# BLOCK1.net
KiCad netlist of a schematic drawn in Altium Designer
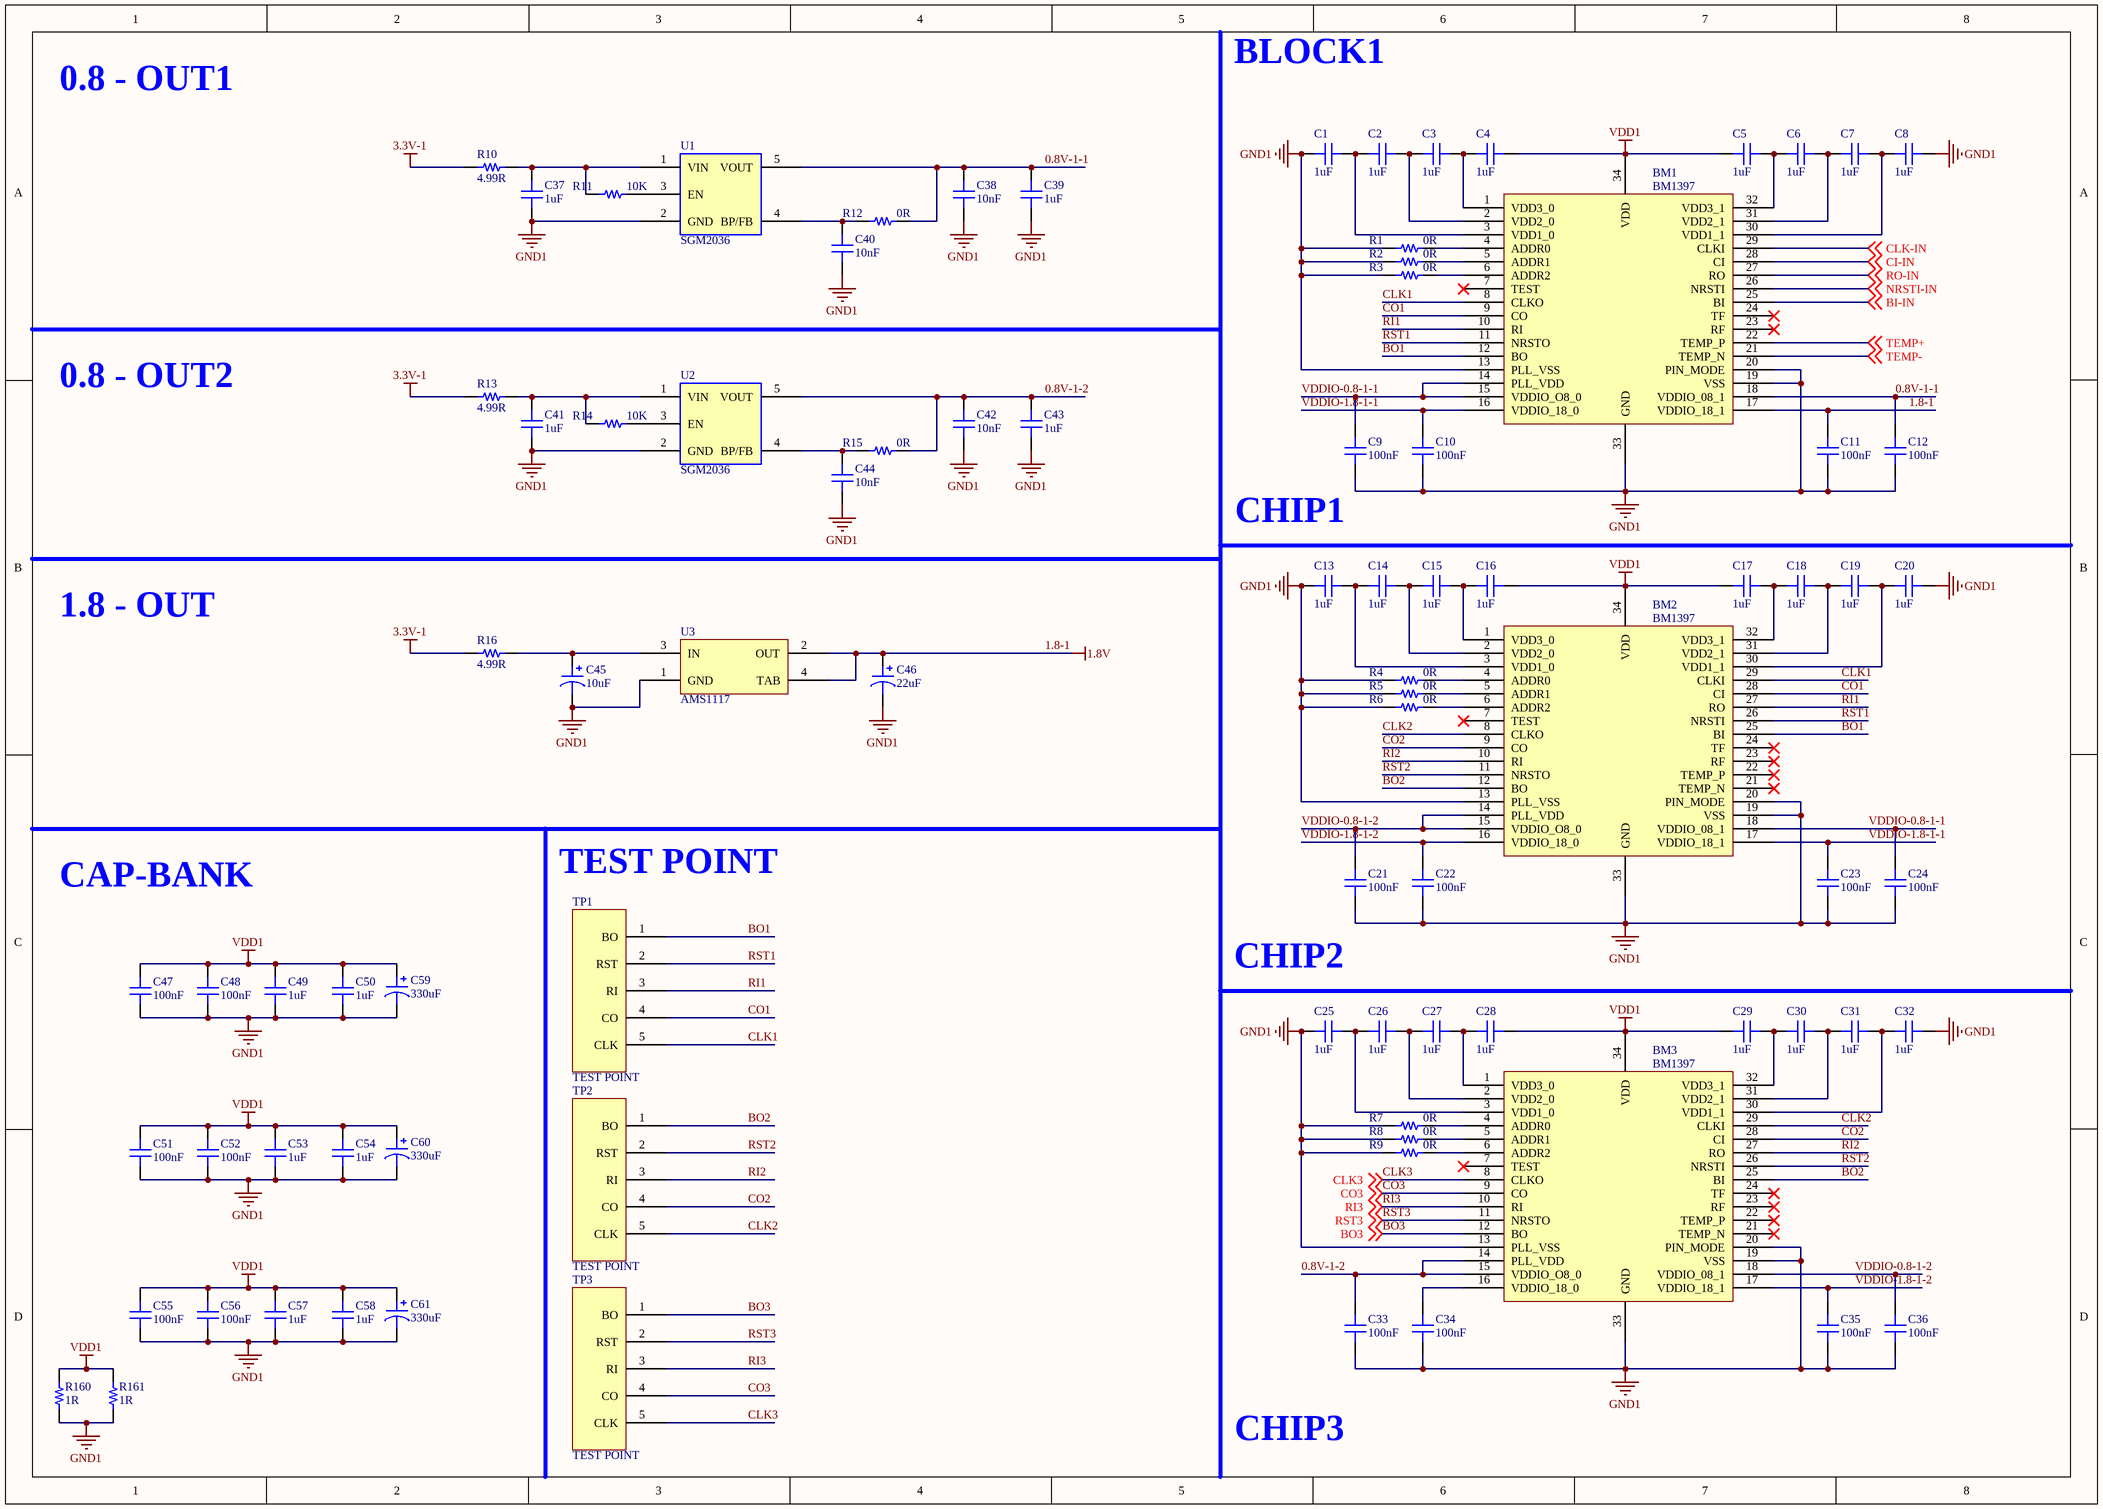
[diagram p0: BLOCK1.SchDoc]

(export (version "E")
  (design (tool "Eeschema 10.0.6"))
  (components
    (comp (ref "BM1") (value "BM1397") (footprint "BM1387") (libsource (lib "Miner_8TH") (part "BM1397_0")))
    (comp (ref "BM2") (value "BM1397") (footprint "BM1387") (libsource (lib "Miner_8TH") (part "BM1397_0")))
    (comp (ref "BM3") (value "BM1397") (footprint "BM1387") (libsource (lib "Miner_8TH") (part "BM1397_0")))
    (comp (ref "C1") (value "1uF") (footprint "CAP-SMD-0603") (libsource (lib "Miner_8TH") (part "CAP")))
    (comp (ref "C2") (value "1uF") (footprint "CAP-SMD-0603") (libsource (lib "Miner_8TH") (part "CAP")))
    (comp (ref "C3") (value "1uF") (footprint "CAP-SMD-0603") (libsource (lib "Miner_8TH") (part "CAP")))
    (comp (ref "C4") (value "1uF") (footprint "CAP-SMD-0603") (libsource (lib "Miner_8TH") (part "CAP")))
    (comp (ref "C5") (value "1uF") (footprint "CAP-SMD-0603") (libsource (lib "Miner_8TH") (part "CAP")))
    (comp (ref "C6") (value "1uF") (footprint "CAP-SMD-0603") (libsource (lib "Miner_8TH") (part "CAP")))
    (comp (ref "C7") (value "1uF") (footprint "CAP-SMD-0603") (libsource (lib "Miner_8TH") (part "CAP")))
    (comp (ref "C8") (value "1uF") (footprint "CAP-SMD-0603") (libsource (lib "Miner_8TH") (part "CAP")))
    (comp (ref "C9") (value "100nF") (footprint "CAP_SMD_0805") (libsource (lib "Miner_8TH") (part "CAP")))
    (comp (ref "C10") (value "100nF") (footprint "CAP_SMD_0805") (libsource (lib "Miner_8TH") (part "CAP")))
    (comp (ref "C11") (value "100nF") (footprint "CAP_SMD_0805") (libsource (lib "Miner_8TH") (part "CAP")))
    (comp (ref "C12") (value "100nF") (footprint "CAP_SMD_0805") (libsource (lib "Miner_8TH") (part "CAP")))
    (comp (ref "C13") (value "1uF") (footprint "CAP-SMD-0603") (libsource (lib "Miner_8TH") (part "CAP")))
    (comp (ref "C14") (value "1uF") (footprint "CAP-SMD-0603") (libsource (lib "Miner_8TH") (part "CAP")))
    (comp (ref "C15") (value "1uF") (footprint "CAP-SMD-0603") (libsource (lib "Miner_8TH") (part "CAP")))
    (comp (ref "C16") (value "1uF") (footprint "CAP-SMD-0603") (libsource (lib "Miner_8TH") (part "CAP")))
    (comp (ref "C17") (value "1uF") (footprint "CAP-SMD-0603") (libsource (lib "Miner_8TH") (part "CAP")))
    (comp (ref "C18") (value "1uF") (footprint "CAP-SMD-0603") (libsource (lib "Miner_8TH") (part "CAP")))
    (comp (ref "C19") (value "1uF") (footprint "CAP-SMD-0603") (libsource (lib "Miner_8TH") (part "CAP")))
    (comp (ref "C20") (value "1uF") (footprint "CAP-SMD-0603") (libsource (lib "Miner_8TH") (part "CAP")))
    (comp (ref "C21") (value "100nF") (footprint "CAP_SMD_0805") (libsource (lib "Miner_8TH") (part "CAP")))
    (comp (ref "C22") (value "100nF") (footprint "CAP_SMD_0805") (libsource (lib "Miner_8TH") (part "CAP")))
    (comp (ref "C23") (value "100nF") (footprint "CAP_SMD_0805") (libsource (lib "Miner_8TH") (part "CAP")))
    (comp (ref "C24") (value "100nF") (footprint "CAP_SMD_0805") (libsource (lib "Miner_8TH") (part "CAP")))
    (comp (ref "C25") (value "1uF") (footprint "CAP-SMD-0603") (libsource (lib "Miner_8TH") (part "CAP")))
    (comp (ref "C26") (value "1uF") (footprint "CAP-SMD-0603") (libsource (lib "Miner_8TH") (part "CAP")))
    (comp (ref "C27") (value "1uF") (footprint "CAP-SMD-0603") (libsource (lib "Miner_8TH") (part "CAP")))
    (comp (ref "C28") (value "1uF") (footprint "CAP-SMD-0603") (libsource (lib "Miner_8TH") (part "CAP")))
    (comp (ref "C29") (value "1uF") (footprint "CAP-SMD-0603") (libsource (lib "Miner_8TH") (part "CAP")))
    (comp (ref "C30") (value "1uF") (footprint "CAP-SMD-0603") (libsource (lib "Miner_8TH") (part "CAP")))
    (comp (ref "C31") (value "1uF") (footprint "CAP-SMD-0603") (libsource (lib "Miner_8TH") (part "CAP")))
    (comp (ref "C32") (value "1uF") (footprint "CAP-SMD-0603") (libsource (lib "Miner_8TH") (part "CAP")))
    (comp (ref "C33") (value "100nF") (footprint "CAP_SMD_0805") (libsource (lib "Miner_8TH") (part "CAP")))
    (comp (ref "C34") (value "100nF") (footprint "CAP_SMD_0805") (libsource (lib "Miner_8TH") (part "CAP")))
    (comp (ref "C35") (value "100nF") (footprint "CAP_SMD_0805") (libsource (lib "Miner_8TH") (part "CAP")))
    (comp (ref "C36") (value "100nF") (footprint "CAP_SMD_0805") (libsource (lib "Miner_8TH") (part "CAP")))
    (comp (ref "C37") (value "1uF") (footprint "CAP_SMD_0805") (libsource (lib "Miner_8TH") (part "CAP")))
    (comp (ref "C38") (value "10nF") (footprint "CAP_SMD_0805") (libsource (lib "Miner_8TH") (part "CAP")))
    (comp (ref "C39") (value "1uF") (footprint "CAP_SMD_0805") (libsource (lib "Miner_8TH") (part "CAP")))
    (comp (ref "C40") (value "10nF") (footprint "CAP_SMD_0805") (libsource (lib "Miner_8TH") (part "CAP")))
    (comp (ref "C41") (value "1uF") (footprint "CAP_SMD_0805") (libsource (lib "Miner_8TH") (part "CAP")))
    (comp (ref "C42") (value "10nF") (footprint "CAP_SMD_0805") (libsource (lib "Miner_8TH") (part "CAP")))
    (comp (ref "C43") (value "1uF") (footprint "CAP_SMD_0805") (libsource (lib "Miner_8TH") (part "CAP")))
    (comp (ref "C44") (value "10nF") (footprint "CAP_SMD_0805") (libsource (lib "Miner_8TH") (part "CAP")))
    (comp (ref "C45")
      (value "10uF")
      (footprint "CAP-TAN-CASE-A")
      (libsource (lib "Miner_8TH") (part "POLARIZED CAP"))
    )
    (comp (ref "C46")
      (value "22uF")
      (footprint "CAP-TAN-CASE-A")
      (libsource (lib "Miner_8TH") (part "POLARIZED CAP"))
    )
    (comp (ref "C47") (value "100nF") (footprint "CAP_SMD_0805") (libsource (lib "Miner_8TH") (part "CAP")))
    (comp (ref "C48") (value "100nF") (footprint "CAP_SMD_0805") (libsource (lib "Miner_8TH") (part "CAP")))
    (comp (ref "C49") (value "1uF") (footprint "CAP_SMD_0805") (libsource (lib "Miner_8TH") (part "CAP")))
    (comp (ref "C50") (value "1uF") (footprint "CAP_SMD_0805") (libsource (lib "Miner_8TH") (part "CAP")))
    (comp (ref "C51") (value "100nF") (footprint "CAP_SMD_0805") (libsource (lib "Miner_8TH") (part "CAP")))
    (comp (ref "C52") (value "100nF") (footprint "CAP_SMD_0805") (libsource (lib "Miner_8TH") (part "CAP")))
    (comp (ref "C53") (value "1uF") (footprint "CAP_SMD_0805") (libsource (lib "Miner_8TH") (part "CAP")))
    (comp (ref "C54") (value "1uF") (footprint "CAP_SMD_0805") (libsource (lib "Miner_8TH") (part "CAP")))
    (comp (ref "C55") (value "100nF") (footprint "CAP_SMD_0805") (libsource (lib "Miner_8TH") (part "CAP")))
    (comp (ref "C56") (value "100nF") (footprint "CAP_SMD_0805") (libsource (lib "Miner_8TH") (part "CAP")))
    (comp (ref "C57") (value "1uF") (footprint "CAP_SMD_0805") (libsource (lib "Miner_8TH") (part "CAP")))
    (comp (ref "C58") (value "1uF") (footprint "CAP_SMD_0805") (libsource (lib "Miner_8TH") (part "CAP")))
    (comp (ref "C59")
      (value "330uF")
      (footprint "CAP-TAN-CASE-E")
      (libsource (lib "Miner_8TH") (part "POLARIZED CAP"))
    )
    (comp (ref "C60")
      (value "330uF")
      (footprint "CAP-TAN-CASE-E")
      (libsource (lib "Miner_8TH") (part "POLARIZED CAP"))
    )
    (comp (ref "C61")
      (value "330uF")
      (footprint "CAP-TAN-CASE-E")
      (libsource (lib "Miner_8TH") (part "POLARIZED CAP"))
    )
    (comp (ref "R1") (value "0R") (footprint "RES-SMD-0402") (libsource (lib "Miner_8TH") (part "RES")))
    (comp (ref "R2") (value "0R") (footprint "RES-SMD-0402") (libsource (lib "Miner_8TH") (part "RES")))
    (comp (ref "R3") (value "0R") (footprint "RES-SMD-0402") (libsource (lib "Miner_8TH") (part "RES")))
    (comp (ref "R4") (value "0R") (footprint "RES-SMD-0402") (libsource (lib "Miner_8TH") (part "RES")))
    (comp (ref "R5") (value "0R") (footprint "RES-SMD-0402") (libsource (lib "Miner_8TH") (part "RES")))
    (comp (ref "R6") (value "0R") (footprint "RES-SMD-0402") (libsource (lib "Miner_8TH") (part "RES")))
    (comp (ref "R7") (value "0R") (footprint "RES-SMD-0402") (libsource (lib "Miner_8TH") (part "RES")))
    (comp (ref "R8") (value "0R") (footprint "RES-SMD-0402") (libsource (lib "Miner_8TH") (part "RES")))
    (comp (ref "R9") (value "0R") (footprint "RES-SMD-0402") (libsource (lib "Miner_8TH") (part "RES")))
    (comp (ref "R10") (value "4.99R") (footprint "RES-SMD-1206") (libsource (lib "Miner_8TH") (part "RES")))
    (comp (ref "R11") (value "10K") (footprint "RES-SMD-0402") (libsource (lib "Miner_8TH") (part "RES")))
    (comp (ref "R12") (value "0R") (footprint "RES-SMD-0402") (libsource (lib "Miner_8TH") (part "RES")))
    (comp (ref "R13") (value "4.99R") (footprint "RES-SMD-1206") (libsource (lib "Miner_8TH") (part "RES")))
    (comp (ref "R14") (value "10K") (footprint "RES-SMD-0402") (libsource (lib "Miner_8TH") (part "RES")))
    (comp (ref "R15") (value "0R") (footprint "RES-SMD-0402") (libsource (lib "Miner_8TH") (part "RES")))
    (comp (ref "R16") (value "4.99R") (footprint "RES-SMD-1206") (libsource (lib "Miner_8TH") (part "RES")))
    (comp (ref "R160") (value "1R") (footprint "RES-SMD-1210") (libsource (lib "Miner_8TH") (part "RES")))
    (comp (ref "R161") (value "1R") (footprint "RES-SMD-1210") (libsource (lib "Miner_8TH") (part "RES")))
    (comp (ref "TP1")
      (value "TEST POINT")
      (footprint "TEST_POINT")
      (libsource (lib "Miner_8TH") (part "TEST POINT"))
    )
    (comp (ref "TP2")
      (value "TEST POINT")
      (footprint "TEST_POINT")
      (libsource (lib "Miner_8TH") (part "TEST POINT"))
    )
    (comp (ref "TP3")
      (value "TEST POINT")
      (footprint "TEST_POINT")
      (libsource (lib "Miner_8TH") (part "TEST POINT"))
    )
    (comp (ref "U1")
      (value "SGM2036")
      (footprint "SOT23-5PIN")
      (libsource (lib "Miner_8TH") (part "SGM2036"))
    )
    (comp (ref "U2")
      (value "SGM2036")
      (footprint "SOT23-5PIN")
      (libsource (lib "Miner_8TH") (part "SGM2036"))
    )
    (comp (ref "U3") (value "AMS1117") (footprint "AMS1117") (libsource (lib "Miner_8TH") (part "AMS1117")))
  )
  (nets
    (net (code "1") (name "/0.8V-1-1") (class "Default")
      (node (ref "BM1") (pin "18") (pinfunction "VDDIO_08_1_18") (pintype "passive"))
      (node (ref "C12") (pin "2") (pinfunction "2_2") (pintype "passive"))
      (node (ref "C38") (pin "2") (pinfunction "2_2") (pintype "passive"))
      (node (ref "C39") (pin "2") (pinfunction "2_2") (pintype "passive"))
      (node (ref "R12") (pin "2") (pinfunction "2_2") (pintype "passive"))
      (node (ref "U1") (pin "5") (pinfunction "VOUT_5") (pintype "passive"))
    )
    (net (code "2") (name "/0.8V-1-2") (class "Default")
      (node (ref "BM3") (pin "14") (pinfunction "PLL_VDD_14") (pintype "passive"))
      (node (ref "BM3") (pin "15") (pinfunction "VDDIO_O8_0_15") (pintype "passive"))
      (node (ref "C33") (pin "2") (pinfunction "2_2") (pintype "passive"))
      (node (ref "C42") (pin "2") (pinfunction "2_2") (pintype "passive"))
      (node (ref "C43") (pin "2") (pinfunction "2_2") (pintype "passive"))
      (node (ref "R15") (pin "2") (pinfunction "2_2") (pintype "passive"))
      (node (ref "U2") (pin "5") (pinfunction "VOUT_5") (pintype "passive"))
    )
    (net (code "3") (name "/BO1") (class "Default")
      (node (ref "BM1") (pin "12") (pinfunction "BO_12") (pintype "passive"))
      (node (ref "BM2") (pin "25") (pinfunction "BI_25") (pintype "passive"))
      (node (ref "TP1") (pin "1") (pinfunction "BO_1") (pintype "passive"))
    )
    (net (code "4") (name "/BO2") (class "Default")
      (node (ref "BM2") (pin "12") (pinfunction "BO_12") (pintype "passive"))
      (node (ref "BM3") (pin "25") (pinfunction "BI_25") (pintype "passive"))
      (node (ref "TP2") (pin "1") (pinfunction "BO_1") (pintype "passive"))
    )
    (net (code "5") (name "/CLK1") (class "Default")
      (node (ref "BM1") (pin "8") (pinfunction "CLKO_8") (pintype "passive"))
      (node (ref "BM2") (pin "29") (pinfunction "CLKI_29") (pintype "passive"))
      (node (ref "TP1") (pin "5") (pinfunction "CLK_5") (pintype "passive"))
    )
    (net (code "6") (name "/CLK2") (class "Default")
      (node (ref "BM2") (pin "8") (pinfunction "CLKO_8") (pintype "passive"))
      (node (ref "BM3") (pin "29") (pinfunction "CLKI_29") (pintype "passive"))
      (node (ref "TP2") (pin "5") (pinfunction "CLK_5") (pintype "passive"))
    )
    (net (code "7") (name "/CO1") (class "Default")
      (node (ref "BM1") (pin "9") (pinfunction "CO_9") (pintype "passive"))
      (node (ref "BM2") (pin "28") (pinfunction "CI_28") (pintype "passive"))
      (node (ref "TP1") (pin "4") (pinfunction "CO_4") (pintype "passive"))
    )
    (net (code "8") (name "/CO2") (class "Default")
      (node (ref "BM2") (pin "9") (pinfunction "CO_9") (pintype "passive"))
      (node (ref "BM3") (pin "28") (pinfunction "CI_28") (pintype "passive"))
      (node (ref "TP2") (pin "4") (pinfunction "CO_4") (pintype "passive"))
    )
    (net (code "9") (name "/RI1") (class "Default")
      (node (ref "BM1") (pin "10") (pinfunction "RI_10") (pintype "passive"))
      (node (ref "BM2") (pin "27") (pinfunction "RO_27") (pintype "passive"))
      (node (ref "TP1") (pin "3") (pinfunction "RI_3") (pintype "passive"))
    )
    (net (code "10") (name "/RI2") (class "Default")
      (node (ref "BM2") (pin "10") (pinfunction "RI_10") (pintype "passive"))
      (node (ref "BM3") (pin "27") (pinfunction "RO_27") (pintype "passive"))
      (node (ref "TP2") (pin "3") (pinfunction "RI_3") (pintype "passive"))
    )
    (net (code "11") (name "/RST1") (class "Default")
      (node (ref "BM1") (pin "11") (pinfunction "NRSTO_11") (pintype "passive"))
      (node (ref "BM2") (pin "26") (pinfunction "NRSTI_26") (pintype "passive"))
      (node (ref "TP1") (pin "2") (pinfunction "RST_2") (pintype "passive"))
    )
    (net (code "12") (name "/RST2") (class "Default")
      (node (ref "BM2") (pin "11") (pinfunction "NRSTO_11") (pintype "passive"))
      (node (ref "BM3") (pin "26") (pinfunction "NRSTI_26") (pintype "passive"))
      (node (ref "TP2") (pin "2") (pinfunction "RST_2") (pintype "passive"))
    )
    (net (code "13") (name "/VDDIO-0.8-1-1") (class "Default")
      (node (ref "BM1") (pin "14") (pinfunction "PLL_VDD_14") (pintype "passive"))
      (node (ref "BM1") (pin "15") (pinfunction "VDDIO_O8_0_15") (pintype "passive"))
      (node (ref "BM2") (pin "18") (pinfunction "VDDIO_08_1_18") (pintype "passive"))
      (node (ref "C24") (pin "2") (pinfunction "2_2") (pintype "passive"))
      (node (ref "C9") (pin "2") (pinfunction "2_2") (pintype "passive"))
    )
    (net (code "14") (name "/VDDIO-0.8-1-2") (class "Default")
      (node (ref "BM2") (pin "14") (pinfunction "PLL_VDD_14") (pintype "passive"))
      (node (ref "BM2") (pin "15") (pinfunction "VDDIO_O8_0_15") (pintype "passive"))
      (node (ref "BM3") (pin "18") (pinfunction "VDDIO_08_1_18") (pintype "passive"))
      (node (ref "C21") (pin "2") (pinfunction "2_2") (pintype "passive"))
      (node (ref "C36") (pin "2") (pinfunction "2_2") (pintype "passive"))
    )
    (net (code "15") (name "/VDDIO-1.8-1-1") (class "Default")
      (node (ref "BM1") (pin "16") (pinfunction "VDDIO_18_0_16") (pintype "passive"))
      (node (ref "BM2") (pin "17") (pinfunction "VDDIO_18_1_17") (pintype "passive"))
      (node (ref "C10") (pin "2") (pinfunction "2_2") (pintype "passive"))
      (node (ref "C23") (pin "2") (pinfunction "2_2") (pintype "passive"))
    )
    (net (code "16") (name "/VDDIO-1.8-1-2") (class "Default")
      (node (ref "BM2") (pin "16") (pinfunction "VDDIO_18_0_16") (pintype "passive"))
      (node (ref "BM3") (pin "17") (pinfunction "VDDIO_18_1_17") (pintype "passive"))
      (node (ref "C22") (pin "2") (pinfunction "2_2") (pintype "passive"))
      (node (ref "C35") (pin "2") (pinfunction "2_2") (pintype "passive"))
    )
    (net (code "17") (name "1.8V") (class "Default")
      (node (ref "BM1") (pin "17") (pinfunction "VDDIO_18_1_17") (pintype "passive"))
      (node (ref "C11") (pin "2") (pinfunction "2_2") (pintype "passive"))
      (node (ref "C46") (pin "1") (pinfunction "1_1") (pintype "passive"))
      (node (ref "U3") (pin "2") (pinfunction "OUT_2") (pintype "passive"))
      (node (ref "U3") (pin "4") (pinfunction "TAB_4") (pintype "passive"))
    )
    (net (code "18") (name "3.3V-1") (class "Default")
      (node (ref "R10") (pin "1") (pinfunction "1_1") (pintype "passive"))
      (node (ref "R13") (pin "1") (pinfunction "1_1") (pintype "passive"))
      (node (ref "R16") (pin "1") (pinfunction "1_1") (pintype "passive"))
    )
    (net (code "19") (name "BI-IN") (class "Default")
      (node (ref "BM1") (pin "25") (pinfunction "BI_25") (pintype "passive"))
    )
    (net (code "20") (name "BO3") (class "Default")
      (node (ref "BM3") (pin "12") (pinfunction "BO_12") (pintype "passive"))
      (node (ref "TP3") (pin "1") (pinfunction "BO_1") (pintype "passive"))
    )
    (net (code "21") (name "CI-IN") (class "Default")
      (node (ref "BM1") (pin "28") (pinfunction "CI_28") (pintype "passive"))
    )
    (net (code "22") (name "CLK-IN") (class "Default")
      (node (ref "BM1") (pin "29") (pinfunction "CLKI_29") (pintype "passive"))
    )
    (net (code "23") (name "CLK3") (class "Default")
      (node (ref "BM3") (pin "8") (pinfunction "CLKO_8") (pintype "passive"))
      (node (ref "TP3") (pin "5") (pinfunction "CLK_5") (pintype "passive"))
    )
    (net (code "24") (name "CO3") (class "Default")
      (node (ref "BM3") (pin "9") (pinfunction "CO_9") (pintype "passive"))
      (node (ref "TP3") (pin "4") (pinfunction "CO_4") (pintype "passive"))
    )
    (net (code "25") (name "GND1") (class "Default")
      (node (ref "BM1") (pin "13") (pinfunction "PLL_VSS_13") (pintype "passive"))
      (node (ref "BM1") (pin "19") (pinfunction "VSS_19") (pintype "passive"))
      (node (ref "BM1") (pin "20") (pinfunction "PIN_MODE_20") (pintype "passive"))
      (node (ref "BM1") (pin "33") (pinfunction "GND_33") (pintype "passive"))
      (node (ref "BM2") (pin "13") (pinfunction "PLL_VSS_13") (pintype "passive"))
      (node (ref "BM2") (pin "19") (pinfunction "VSS_19") (pintype "passive"))
      (node (ref "BM2") (pin "20") (pinfunction "PIN_MODE_20") (pintype "passive"))
      (node (ref "BM2") (pin "33") (pinfunction "GND_33") (pintype "passive"))
      (node (ref "BM3") (pin "13") (pinfunction "PLL_VSS_13") (pintype "passive"))
      (node (ref "BM3") (pin "19") (pinfunction "VSS_19") (pintype "passive"))
      (node (ref "BM3") (pin "20") (pinfunction "PIN_MODE_20") (pintype "passive"))
      (node (ref "BM3") (pin "33") (pinfunction "GND_33") (pintype "passive"))
      (node (ref "C1") (pin "1") (pinfunction "1_1") (pintype "passive"))
      (node (ref "C10") (pin "1") (pinfunction "1_1") (pintype "passive"))
      (node (ref "C11") (pin "1") (pinfunction "1_1") (pintype "passive"))
      (node (ref "C12") (pin "1") (pinfunction "1_1") (pintype "passive"))
      (node (ref "C13") (pin "1") (pinfunction "1_1") (pintype "passive"))
      (node (ref "C20") (pin "2") (pinfunction "2_2") (pintype "passive"))
      (node (ref "C21") (pin "1") (pinfunction "1_1") (pintype "passive"))
      (node (ref "C22") (pin "1") (pinfunction "1_1") (pintype "passive"))
      (node (ref "C23") (pin "1") (pinfunction "1_1") (pintype "passive"))
      (node (ref "C24") (pin "1") (pinfunction "1_1") (pintype "passive"))
      (node (ref "C25") (pin "1") (pinfunction "1_1") (pintype "passive"))
      (node (ref "C32") (pin "2") (pinfunction "2_2") (pintype "passive"))
      (node (ref "C33") (pin "1") (pinfunction "1_1") (pintype "passive"))
      (node (ref "C34") (pin "1") (pinfunction "1_1") (pintype "passive"))
      (node (ref "C35") (pin "1") (pinfunction "1_1") (pintype "passive"))
      (node (ref "C36") (pin "1") (pinfunction "1_1") (pintype "passive"))
      (node (ref "C37") (pin "1") (pinfunction "1_1") (pintype "passive"))
      (node (ref "C38") (pin "1") (pinfunction "1_1") (pintype "passive"))
      (node (ref "C39") (pin "1") (pinfunction "1_1") (pintype "passive"))
      (node (ref "C40") (pin "1") (pinfunction "1_1") (pintype "passive"))
      (node (ref "C41") (pin "1") (pinfunction "1_1") (pintype "passive"))
      (node (ref "C42") (pin "1") (pinfunction "1_1") (pintype "passive"))
      (node (ref "C43") (pin "1") (pinfunction "1_1") (pintype "passive"))
      (node (ref "C44") (pin "1") (pinfunction "1_1") (pintype "passive"))
      (node (ref "C45") (pin "2") (pinfunction "2_2") (pintype "passive"))
      (node (ref "C46") (pin "2") (pinfunction "2_2") (pintype "passive"))
      (node (ref "C47") (pin "1") (pinfunction "1_1") (pintype "passive"))
      (node (ref "C48") (pin "1") (pinfunction "1_1") (pintype "passive"))
      (node (ref "C49") (pin "1") (pinfunction "1_1") (pintype "passive"))
      (node (ref "C50") (pin "1") (pinfunction "1_1") (pintype "passive"))
      (node (ref "C51") (pin "1") (pinfunction "1_1") (pintype "passive"))
      (node (ref "C52") (pin "1") (pinfunction "1_1") (pintype "passive"))
      (node (ref "C53") (pin "1") (pinfunction "1_1") (pintype "passive"))
      (node (ref "C54") (pin "1") (pinfunction "1_1") (pintype "passive"))
      (node (ref "C55") (pin "1") (pinfunction "1_1") (pintype "passive"))
      (node (ref "C56") (pin "1") (pinfunction "1_1") (pintype "passive"))
      (node (ref "C57") (pin "1") (pinfunction "1_1") (pintype "passive"))
      (node (ref "C58") (pin "1") (pinfunction "1_1") (pintype "passive"))
      (node (ref "C59") (pin "2") (pinfunction "2_2") (pintype "passive"))
      (node (ref "C60") (pin "2") (pinfunction "2_2") (pintype "passive"))
      (node (ref "C61") (pin "2") (pinfunction "2_2") (pintype "passive"))
      (node (ref "C8") (pin "2") (pinfunction "2_2") (pintype "passive"))
      (node (ref "C9") (pin "1") (pinfunction "1_1") (pintype "passive"))
      (node (ref "R1") (pin "1") (pinfunction "1_1") (pintype "passive"))
      (node (ref "R160") (pin "1") (pinfunction "1_1") (pintype "passive"))
      (node (ref "R161") (pin "1") (pinfunction "1_1") (pintype "passive"))
      (node (ref "R2") (pin "1") (pinfunction "1_1") (pintype "passive"))
      (node (ref "R3") (pin "1") (pinfunction "1_1") (pintype "passive"))
      (node (ref "R4") (pin "1") (pinfunction "1_1") (pintype "passive"))
      (node (ref "R5") (pin "1") (pinfunction "1_1") (pintype "passive"))
      (node (ref "R6") (pin "1") (pinfunction "1_1") (pintype "passive"))
      (node (ref "R7") (pin "1") (pinfunction "1_1") (pintype "passive"))
      (node (ref "R8") (pin "1") (pinfunction "1_1") (pintype "passive"))
      (node (ref "R9") (pin "1") (pinfunction "1_1") (pintype "passive"))
      (node (ref "U1") (pin "2") (pinfunction "GND_2") (pintype "passive"))
      (node (ref "U2") (pin "2") (pinfunction "GND_2") (pintype "passive"))
      (node (ref "U3") (pin "1") (pinfunction "GND_1") (pintype "passive"))
    )
    (net (code "26") (name "NRSTI-IN") (class "Default")
      (node (ref "BM1") (pin "26") (pinfunction "NRSTI_26") (pintype "passive"))
    )
    (net (code "27") (name "Net-(BM1-ADDR0)") (class "Default")
      (node (ref "BM1") (pin "4") (pinfunction "ADDR0_4") (pintype "passive"))
      (node (ref "R1") (pin "2") (pinfunction "2_2") (pintype "passive"))
    )
    (net (code "28") (name "Net-(BM1-ADDR1)") (class "Default")
      (node (ref "BM1") (pin "5") (pinfunction "ADDR1_5") (pintype "passive"))
      (node (ref "R2") (pin "2") (pinfunction "2_2") (pintype "passive"))
    )
    (net (code "29") (name "Net-(BM1-ADDR2)") (class "Default")
      (node (ref "BM1") (pin "6") (pinfunction "ADDR2_6") (pintype "passive"))
      (node (ref "R3") (pin "2") (pinfunction "2_2") (pintype "passive"))
    )
    (net (code "30") (name "Net-(BM1-VDD1_0)") (class "Default")
      (node (ref "BM1") (pin "3") (pinfunction "VDD1_0_3") (pintype "passive"))
      (node (ref "C1") (pin "2") (pinfunction "2_2") (pintype "passive"))
      (node (ref "C2") (pin "1") (pinfunction "1_1") (pintype "passive"))
    )
    (net (code "31") (name "Net-(BM1-VDD1_1)") (class "Default")
      (node (ref "BM1") (pin "30") (pinfunction "VDD1_1_30") (pintype "passive"))
      (node (ref "C7") (pin "2") (pinfunction "2_2") (pintype "passive"))
      (node (ref "C8") (pin "1") (pinfunction "1_1") (pintype "passive"))
    )
    (net (code "32") (name "Net-(BM1-VDD2_0)") (class "Default")
      (node (ref "BM1") (pin "2") (pinfunction "VDD2_0_2") (pintype "passive"))
      (node (ref "C2") (pin "2") (pinfunction "2_2") (pintype "passive"))
      (node (ref "C3") (pin "1") (pinfunction "1_1") (pintype "passive"))
    )
    (net (code "33") (name "Net-(BM1-VDD2_1)") (class "Default")
      (node (ref "BM1") (pin "31") (pinfunction "VDD2_1_31") (pintype "passive"))
      (node (ref "C6") (pin "2") (pinfunction "2_2") (pintype "passive"))
      (node (ref "C7") (pin "1") (pinfunction "1_1") (pintype "passive"))
    )
    (net (code "34") (name "Net-(BM1-VDD3_0)") (class "Default")
      (node (ref "BM1") (pin "1") (pinfunction "VDD3_0_1") (pintype "passive"))
      (node (ref "C3") (pin "2") (pinfunction "2_2") (pintype "passive"))
      (node (ref "C4") (pin "1") (pinfunction "1_1") (pintype "passive"))
    )
    (net (code "35") (name "Net-(BM1-VDD3_1)") (class "Default")
      (node (ref "BM1") (pin "32") (pinfunction "VDD3_1_32") (pintype "passive"))
      (node (ref "C5") (pin "2") (pinfunction "2_2") (pintype "passive"))
      (node (ref "C6") (pin "1") (pinfunction "1_1") (pintype "passive"))
    )
    (net (code "36") (name "Net-(BM2-ADDR0)") (class "Default")
      (node (ref "BM2") (pin "4") (pinfunction "ADDR0_4") (pintype "passive"))
      (node (ref "R4") (pin "2") (pinfunction "2_2") (pintype "passive"))
    )
    (net (code "37") (name "Net-(BM2-ADDR1)") (class "Default")
      (node (ref "BM2") (pin "5") (pinfunction "ADDR1_5") (pintype "passive"))
      (node (ref "R5") (pin "2") (pinfunction "2_2") (pintype "passive"))
    )
    (net (code "38") (name "Net-(BM2-ADDR2)") (class "Default")
      (node (ref "BM2") (pin "6") (pinfunction "ADDR2_6") (pintype "passive"))
      (node (ref "R6") (pin "2") (pinfunction "2_2") (pintype "passive"))
    )
    (net (code "39") (name "Net-(BM2-VDD1_0)") (class "Default")
      (node (ref "BM2") (pin "3") (pinfunction "VDD1_0_3") (pintype "passive"))
      (node (ref "C13") (pin "2") (pinfunction "2_2") (pintype "passive"))
      (node (ref "C14") (pin "1") (pinfunction "1_1") (pintype "passive"))
    )
    (net (code "40") (name "Net-(BM2-VDD1_1)") (class "Default")
      (node (ref "BM2") (pin "30") (pinfunction "VDD1_1_30") (pintype "passive"))
      (node (ref "C19") (pin "2") (pinfunction "2_2") (pintype "passive"))
      (node (ref "C20") (pin "1") (pinfunction "1_1") (pintype "passive"))
    )
    (net (code "41") (name "Net-(BM2-VDD2_0)") (class "Default")
      (node (ref "BM2") (pin "2") (pinfunction "VDD2_0_2") (pintype "passive"))
      (node (ref "C14") (pin "2") (pinfunction "2_2") (pintype "passive"))
      (node (ref "C15") (pin "1") (pinfunction "1_1") (pintype "passive"))
    )
    (net (code "42") (name "Net-(BM2-VDD2_1)") (class "Default")
      (node (ref "BM2") (pin "31") (pinfunction "VDD2_1_31") (pintype "passive"))
      (node (ref "C18") (pin "2") (pinfunction "2_2") (pintype "passive"))
      (node (ref "C19") (pin "1") (pinfunction "1_1") (pintype "passive"))
    )
    (net (code "43") (name "Net-(BM2-VDD3_0)") (class "Default")
      (node (ref "BM2") (pin "1") (pinfunction "VDD3_0_1") (pintype "passive"))
      (node (ref "C15") (pin "2") (pinfunction "2_2") (pintype "passive"))
      (node (ref "C16") (pin "1") (pinfunction "1_1") (pintype "passive"))
    )
    (net (code "44") (name "Net-(BM2-VDD3_1)") (class "Default")
      (node (ref "BM2") (pin "32") (pinfunction "VDD3_1_32") (pintype "passive"))
      (node (ref "C17") (pin "2") (pinfunction "2_2") (pintype "passive"))
      (node (ref "C18") (pin "1") (pinfunction "1_1") (pintype "passive"))
    )
    (net (code "45") (name "Net-(BM3-ADDR0)") (class "Default")
      (node (ref "BM3") (pin "4") (pinfunction "ADDR0_4") (pintype "passive"))
      (node (ref "R7") (pin "2") (pinfunction "2_2") (pintype "passive"))
    )
    (net (code "46") (name "Net-(BM3-ADDR1)") (class "Default")
      (node (ref "BM3") (pin "5") (pinfunction "ADDR1_5") (pintype "passive"))
      (node (ref "R8") (pin "2") (pinfunction "2_2") (pintype "passive"))
    )
    (net (code "47") (name "Net-(BM3-ADDR2)") (class "Default")
      (node (ref "BM3") (pin "6") (pinfunction "ADDR2_6") (pintype "passive"))
      (node (ref "R9") (pin "2") (pinfunction "2_2") (pintype "passive"))
    )
    (net (code "48") (name "Net-(BM3-VDD1_0)") (class "Default")
      (node (ref "BM3") (pin "3") (pinfunction "VDD1_0_3") (pintype "passive"))
      (node (ref "C25") (pin "2") (pinfunction "2_2") (pintype "passive"))
      (node (ref "C26") (pin "1") (pinfunction "1_1") (pintype "passive"))
    )
    (net (code "49") (name "Net-(BM3-VDD1_1)") (class "Default")
      (node (ref "BM3") (pin "30") (pinfunction "VDD1_1_30") (pintype "passive"))
      (node (ref "C31") (pin "2") (pinfunction "2_2") (pintype "passive"))
      (node (ref "C32") (pin "1") (pinfunction "1_1") (pintype "passive"))
    )
    (net (code "50") (name "Net-(BM3-VDD2_0)") (class "Default")
      (node (ref "BM3") (pin "2") (pinfunction "VDD2_0_2") (pintype "passive"))
      (node (ref "C26") (pin "2") (pinfunction "2_2") (pintype "passive"))
      (node (ref "C27") (pin "1") (pinfunction "1_1") (pintype "passive"))
    )
    (net (code "51") (name "Net-(BM3-VDD2_1)") (class "Default")
      (node (ref "BM3") (pin "31") (pinfunction "VDD2_1_31") (pintype "passive"))
      (node (ref "C30") (pin "2") (pinfunction "2_2") (pintype "passive"))
      (node (ref "C31") (pin "1") (pinfunction "1_1") (pintype "passive"))
    )
    (net (code "52") (name "Net-(BM3-VDD3_0)") (class "Default")
      (node (ref "BM3") (pin "1") (pinfunction "VDD3_0_1") (pintype "passive"))
      (node (ref "C27") (pin "2") (pinfunction "2_2") (pintype "passive"))
      (node (ref "C28") (pin "1") (pinfunction "1_1") (pintype "passive"))
    )
    (net (code "53") (name "Net-(BM3-VDD3_1)") (class "Default")
      (node (ref "BM3") (pin "32") (pinfunction "VDD3_1_32") (pintype "passive"))
      (node (ref "C29") (pin "2") (pinfunction "2_2") (pintype "passive"))
      (node (ref "C30") (pin "1") (pinfunction "1_1") (pintype "passive"))
    )
    (net (code "54") (name "Net-(BM3-VDDIO_18_0)") (class "Default")
      (node (ref "BM3") (pin "16") (pinfunction "VDDIO_18_0_16") (pintype "passive"))
      (node (ref "C34") (pin "2") (pinfunction "2_2") (pintype "passive"))
    )
    (net (code "55") (name "Net-(U1-BP{slash}FB)") (class "Default")
      (node (ref "C40") (pin "2") (pinfunction "2_2") (pintype "passive"))
      (node (ref "R12") (pin "1") (pinfunction "1_1") (pintype "passive"))
      (node (ref "U1") (pin "4") (pinfunction "BP/FB_4") (pintype "passive"))
    )
    (net (code "56") (name "Net-(U1-EN)") (class "Default")
      (node (ref "R11") (pin "2") (pinfunction "2_2") (pintype "passive"))
      (node (ref "U1") (pin "3") (pinfunction "EN_3") (pintype "passive"))
    )
    (net (code "57") (name "Net-(U1-VIN)") (class "Default")
      (node (ref "C37") (pin "2") (pinfunction "2_2") (pintype "passive"))
      (node (ref "R10") (pin "2") (pinfunction "2_2") (pintype "passive"))
      (node (ref "R11") (pin "1") (pinfunction "1_1") (pintype "passive"))
      (node (ref "U1") (pin "1") (pinfunction "VIN_1") (pintype "passive"))
    )
    (net (code "58") (name "Net-(U2-BP{slash}FB)") (class "Default")
      (node (ref "C44") (pin "2") (pinfunction "2_2") (pintype "passive"))
      (node (ref "R15") (pin "1") (pinfunction "1_1") (pintype "passive"))
      (node (ref "U2") (pin "4") (pinfunction "BP/FB_4") (pintype "passive"))
    )
    (net (code "59") (name "Net-(U2-EN)") (class "Default")
      (node (ref "R14") (pin "2") (pinfunction "2_2") (pintype "passive"))
      (node (ref "U2") (pin "3") (pinfunction "EN_3") (pintype "passive"))
    )
    (net (code "60") (name "Net-(U2-VIN)") (class "Default")
      (node (ref "C41") (pin "2") (pinfunction "2_2") (pintype "passive"))
      (node (ref "R13") (pin "2") (pinfunction "2_2") (pintype "passive"))
      (node (ref "R14") (pin "1") (pinfunction "1_1") (pintype "passive"))
      (node (ref "U2") (pin "1") (pinfunction "VIN_1") (pintype "passive"))
    )
    (net (code "61") (name "Net-(U3-IN)") (class "Default")
      (node (ref "C45") (pin "1") (pinfunction "1_1") (pintype "passive"))
      (node (ref "R16") (pin "2") (pinfunction "2_2") (pintype "passive"))
      (node (ref "U3") (pin "3") (pinfunction "IN_3") (pintype "passive"))
    )
    (net (code "62") (name "RI3") (class "Default")
      (node (ref "BM3") (pin "10") (pinfunction "RI_10") (pintype "passive"))
      (node (ref "TP3") (pin "3") (pinfunction "RI_3") (pintype "passive"))
    )
    (net (code "63") (name "RO-IN") (class "Default")
      (node (ref "BM1") (pin "27") (pinfunction "RO_27") (pintype "passive"))
    )
    (net (code "64") (name "RST3") (class "Default")
      (node (ref "BM3") (pin "11") (pinfunction "NRSTO_11") (pintype "passive"))
      (node (ref "TP3") (pin "2") (pinfunction "RST_2") (pintype "passive"))
    )
    (net (code "65") (name "TEMP+") (class "Default")
      (node (ref "BM1") (pin "22") (pinfunction "TEMP_P_22") (pintype "passive"))
    )
    (net (code "66") (name "TEMP-") (class "Default")
      (node (ref "BM1") (pin "21") (pinfunction "TEMP_N_21") (pintype "passive"))
    )
    (net (code "67") (name "VDD1") (class "Default")
      (node (ref "BM1") (pin "34") (pinfunction "VDD_34") (pintype "passive"))
      (node (ref "BM2") (pin "34") (pinfunction "VDD_34") (pintype "passive"))
      (node (ref "BM3") (pin "34") (pinfunction "VDD_34") (pintype "passive"))
      (node (ref "C16") (pin "2") (pinfunction "2_2") (pintype "passive"))
      (node (ref "C17") (pin "1") (pinfunction "1_1") (pintype "passive"))
      (node (ref "C28") (pin "2") (pinfunction "2_2") (pintype "passive"))
      (node (ref "C29") (pin "1") (pinfunction "1_1") (pintype "passive"))
      (node (ref "C4") (pin "2") (pinfunction "2_2") (pintype "passive"))
      (node (ref "C47") (pin "2") (pinfunction "2_2") (pintype "passive"))
      (node (ref "C48") (pin "2") (pinfunction "2_2") (pintype "passive"))
      (node (ref "C49") (pin "2") (pinfunction "2_2") (pintype "passive"))
      (node (ref "C5") (pin "1") (pinfunction "1_1") (pintype "passive"))
      (node (ref "C50") (pin "2") (pinfunction "2_2") (pintype "passive"))
      (node (ref "C51") (pin "2") (pinfunction "2_2") (pintype "passive"))
      (node (ref "C52") (pin "2") (pinfunction "2_2") (pintype "passive"))
      (node (ref "C53") (pin "2") (pinfunction "2_2") (pintype "passive"))
      (node (ref "C54") (pin "2") (pinfunction "2_2") (pintype "passive"))
      (node (ref "C55") (pin "2") (pinfunction "2_2") (pintype "passive"))
      (node (ref "C56") (pin "2") (pinfunction "2_2") (pintype "passive"))
      (node (ref "C57") (pin "2") (pinfunction "2_2") (pintype "passive"))
      (node (ref "C58") (pin "2") (pinfunction "2_2") (pintype "passive"))
      (node (ref "C59") (pin "1") (pinfunction "1_1") (pintype "passive"))
      (node (ref "C60") (pin "1") (pinfunction "1_1") (pintype "passive"))
      (node (ref "C61") (pin "1") (pinfunction "1_1") (pintype "passive"))
      (node (ref "R160") (pin "2") (pinfunction "2_2") (pintype "passive"))
      (node (ref "R161") (pin "2") (pinfunction "2_2") (pintype "passive"))
    )
    (net (code "68") (name "unconnected-(BM1-RF-Pad23)") (class "Default")
      (node (ref "BM1") (pin "23") (pinfunction "RF_23") (pintype "passive+no_connect"))
    )
    (net (code "69") (name "unconnected-(BM1-TEST-Pad7)") (class "Default")
      (node (ref "BM1") (pin "7") (pinfunction "TEST_7") (pintype "passive+no_connect"))
    )
    (net (code "70") (name "unconnected-(BM1-TF-Pad24)") (class "Default")
      (node (ref "BM1") (pin "24") (pinfunction "TF_24") (pintype "passive+no_connect"))
    )
    (net (code "71") (name "unconnected-(BM2-RF-Pad23)") (class "Default")
      (node (ref "BM2") (pin "23") (pinfunction "RF_23") (pintype "passive+no_connect"))
    )
    (net (code "72") (name "unconnected-(BM2-TEMP_N-Pad21)") (class "Default")
      (node (ref "BM2") (pin "21") (pinfunction "TEMP_N_21") (pintype "passive+no_connect"))
    )
    (net (code "73") (name "unconnected-(BM2-TEMP_P-Pad22)") (class "Default")
      (node (ref "BM2") (pin "22") (pinfunction "TEMP_P_22") (pintype "passive+no_connect"))
    )
    (net (code "74") (name "unconnected-(BM2-TEST-Pad7)") (class "Default")
      (node (ref "BM2") (pin "7") (pinfunction "TEST_7") (pintype "passive+no_connect"))
    )
    (net (code "75") (name "unconnected-(BM2-TF-Pad24)") (class "Default")
      (node (ref "BM2") (pin "24") (pinfunction "TF_24") (pintype "passive+no_connect"))
    )
    (net (code "76") (name "unconnected-(BM3-RF-Pad23)") (class "Default")
      (node (ref "BM3") (pin "23") (pinfunction "RF_23") (pintype "passive+no_connect"))
    )
    (net (code "77") (name "unconnected-(BM3-TEMP_N-Pad21)") (class "Default")
      (node (ref "BM3") (pin "21") (pinfunction "TEMP_N_21") (pintype "passive+no_connect"))
    )
    (net (code "78") (name "unconnected-(BM3-TEMP_P-Pad22)") (class "Default")
      (node (ref "BM3") (pin "22") (pinfunction "TEMP_P_22") (pintype "passive+no_connect"))
    )
    (net (code "79") (name "unconnected-(BM3-TEST-Pad7)") (class "Default")
      (node (ref "BM3") (pin "7") (pinfunction "TEST_7") (pintype "passive+no_connect"))
    )
    (net (code "80") (name "unconnected-(BM3-TF-Pad24)") (class "Default")
      (node (ref "BM3") (pin "24") (pinfunction "TF_24") (pintype "passive+no_connect"))
    )
  )
)
